# OwlPedal2.net
KiCad netlist of a schematic drawn in EAGLE
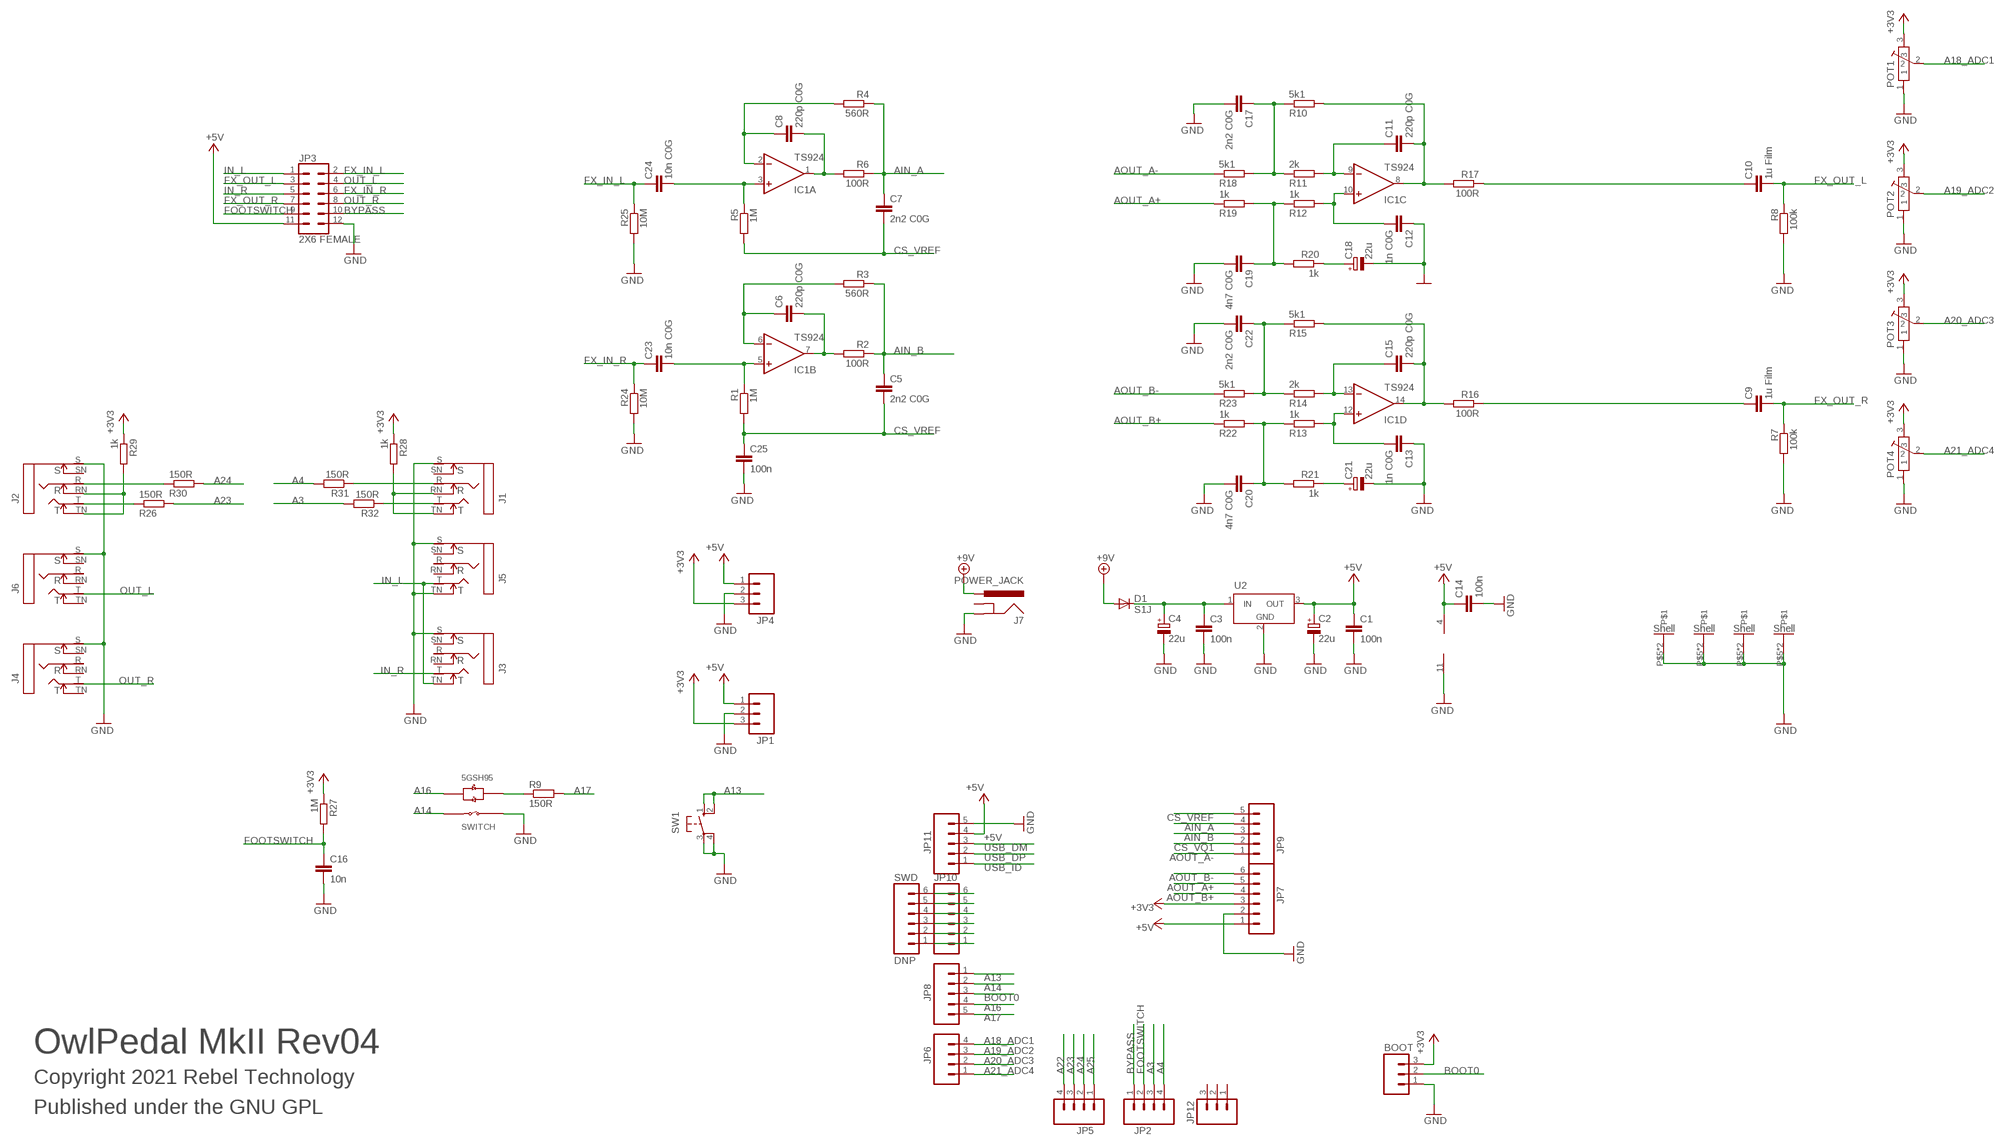
[diagram p0: schematic, sheet 1]

(export (version "E")
  (design (tool "Eeschema 10.0.6"))
  (components
    (comp (ref "BOOT")
      (value "M03PTH")
      (footprint "eagle-import:1X03")
      (libsource (lib "eagle-import") (part "M03PTH"))
    )
    (comp (ref "C1")
      (value "100n")
      (footprint "eagle-import:C0603")
      (libsource (lib "eagle-import") (part "C-EUC0603"))
    )
    (comp (ref "C2")
      (value "22u")
      (footprint "eagle-import:CPOL-5")
      (libsource (lib "eagle-import") (part "CPOL-EU153CLV-0505"))
    )
    (comp (ref "C3")
      (value "100n")
      (footprint "eagle-import:C0603")
      (libsource (lib "eagle-import") (part "C-EUC0603"))
    )
    (comp (ref "C4")
      (value "22u")
      (footprint "eagle-import:CPOL-5")
      (libsource (lib "eagle-import") (part "CPOL-EU153CLV-0505"))
    )
    (comp (ref "C5")
      (value "2n2 C0G")
      (footprint "eagle-import:C0603")
      (libsource (lib "eagle-import") (part "resistor_C-EUC0603"))
    )
    (comp (ref "C6")
      (value "220p C0G")
      (footprint "eagle-import:C0603")
      (libsource (lib "eagle-import") (part "resistor_C-EUC0603"))
    )
    (comp (ref "C7")
      (value "2n2 C0G")
      (footprint "eagle-import:C0603")
      (libsource (lib "eagle-import") (part "resistor_C-EUC0603"))
    )
    (comp (ref "C8")
      (value "220p C0G")
      (footprint "eagle-import:C0603")
      (libsource (lib "eagle-import") (part "resistor_C-EUC0603"))
    )
    (comp (ref "C9")
      (value "1u Film")
      (footprint "eagle-import:C1210")
      (libsource (lib "eagle-import") (part "C-EUC1210"))
    )
    (comp (ref "C10")
      (value "1u Film")
      (footprint "eagle-import:C1210")
      (libsource (lib "eagle-import") (part "C-EUC1210"))
    )
    (comp (ref "C11")
      (value "220p C0G")
      (footprint "eagle-import:C0603")
      (libsource (lib "eagle-import") (part "resistor_C-EUC0603"))
    )
    (comp (ref "C12")
      (value "1n C0G")
      (footprint "eagle-import:C0603")
      (libsource (lib "eagle-import") (part "resistor_C-EUC0603"))
    )
    (comp (ref "C13")
      (value "1n C0G")
      (footprint "eagle-import:C0603")
      (libsource (lib "eagle-import") (part "resistor_C-EUC0603"))
    )
    (comp (ref "C14")
      (value "100n")
      (footprint "eagle-import:C0603")
      (libsource (lib "eagle-import") (part "resistor_C-EUC0603"))
    )
    (comp (ref "C15")
      (value "220p C0G")
      (footprint "eagle-import:C0603")
      (libsource (lib "eagle-import") (part "resistor_C-EUC0603"))
    )
    (comp (ref "C16")
      (value "10n")
      (footprint "eagle-import:C0603")
      (libsource (lib "eagle-import") (part "Rebel_15457297_C-EUC0603"))
    )
    (comp (ref "C17")
      (value "2n2 C0G")
      (footprint "eagle-import:C0603")
      (libsource (lib "eagle-import") (part "resistor_C-EUC0603"))
    )
    (comp (ref "C18")
      (value "22u")
      (footprint "eagle-import:CPOL-5")
      (libsource (lib "eagle-import") (part "CPOL-EU153CLV-0505"))
    )
    (comp (ref "C19")
      (value "4n7 C0G")
      (footprint "eagle-import:C0603")
      (libsource (lib "eagle-import") (part "resistor_C-EUC0603"))
    )
    (comp (ref "C20")
      (value "4n7 C0G")
      (footprint "eagle-import:C0603")
      (libsource (lib "eagle-import") (part "resistor_C-EUC0603"))
    )
    (comp (ref "C21")
      (value "22u")
      (footprint "eagle-import:CPOL-5")
      (libsource (lib "eagle-import") (part "CPOL-EU153CLV-0505"))
    )
    (comp (ref "C22")
      (value "2n2 C0G")
      (footprint "eagle-import:C0603")
      (libsource (lib "eagle-import") (part "resistor_C-EUC0603"))
    )
    (comp (ref "C23")
      (value "10n C0G")
      (footprint "eagle-import:C0603")
      (libsource (lib "eagle-import") (part "C-EUC0603"))
    )
    (comp (ref "C24")
      (value "10n C0G")
      (footprint "eagle-import:C0603")
      (libsource (lib "eagle-import") (part "C-EUC0603"))
    )
    (comp (ref "C25")
      (value "100n")
      (footprint "eagle-import:C0603")
      (libsource (lib "eagle-import") (part "C-EUC0603"))
    )
    (comp (ref "D1")
      (value "S1J")
      (footprint "eagle-import:SMA-DIODE")
      (libsource (lib "eagle-import") (part "DIODESMA"))
    )
    (comp (ref "IC1")
      (value "TS924")
      (footprint "eagle-import:SO14")
      (libsource (lib "eagle-import") (part "LM324D"))
    )
    (comp (ref "J1")
      (value "NEUTRIK_NMJ6HCD2")
      (footprint "eagle-import:NMJ6HCD2")
      (libsource (lib "eagle-import") (part "NEUTRIK_NMJ6HCD2"))
    )
    (comp (ref "J2")
      (value "NEUTRIK_NMJ6HCD2")
      (footprint "eagle-import:NMJ6HCD2")
      (libsource (lib "eagle-import") (part "NEUTRIK_NMJ6HCD2"))
    )
    (comp (ref "J3")
      (value "NEUTRIK_NMJ6HCD2")
      (footprint "eagle-import:NMJ6HCD2")
      (libsource (lib "eagle-import") (part "NEUTRIK_NMJ6HCD2"))
    )
    (comp (ref "J4")
      (value "NEUTRIK_NMJ6HCD2")
      (footprint "eagle-import:NMJ6HCD2")
      (libsource (lib "eagle-import") (part "NEUTRIK_NMJ6HCD2"))
    )
    (comp (ref "J5")
      (value "NEUTRIK_NMJ6HCD2")
      (footprint "eagle-import:NMJ6HCD2")
      (libsource (lib "eagle-import") (part "NEUTRIK_NMJ6HCD2"))
    )
    (comp (ref "J6")
      (value "NEUTRIK_NMJ6HCD2")
      (footprint "eagle-import:NMJ6HCD2")
      (libsource (lib "eagle-import") (part "NEUTRIK_NMJ6HCD2"))
    )
    (comp (ref "J7")
      (value "POWER_JACK")
      (footprint "eagle-import:DC_JACK_SLOT")
      (libsource (lib "eagle-import") (part "POWER_JACK"))
    )
    (comp (ref "JP1")
      (value "M03PTH")
      (footprint "eagle-import:1X03")
      (libsource (lib "eagle-import") (part "M03PTH"))
    )
    (comp (ref "JP2")
      (value "M04PTH")
      (footprint "eagle-import:1X04")
      (libsource (lib "eagle-import") (part "M04PTH"))
    )
    (comp (ref "JP3")
      (value "2X6 FEMALE")
      (footprint "eagle-import:2X6")
      (libsource (lib "eagle-import") (part "CONN_06X2PTH_FEMALE"))
    )
    (comp (ref "JP4")
      (value "M03PTH")
      (footprint "eagle-import:1X03")
      (libsource (lib "eagle-import") (part "M03PTH"))
    )
    (comp (ref "JP5")
      (value "M04PTH")
      (footprint "eagle-import:1X04")
      (libsource (lib "eagle-import") (part "M04PTH"))
    )
    (comp (ref "JP6")
      (value "M04PTH")
      (footprint "eagle-import:1X04")
      (libsource (lib "eagle-import") (part "M04PTH"))
    )
    (comp (ref "JP7")
      (value "M06SIP")
      (footprint "eagle-import:1X06")
      (libsource (lib "eagle-import") (part "M06SIP"))
    )
    (comp (ref "JP8")
      (value "M05PTH")
      (footprint "eagle-import:1X05")
      (libsource (lib "eagle-import") (part "M05PTH"))
    )
    (comp (ref "JP9")
      (value "M05PTH")
      (footprint "eagle-import:1X05")
      (libsource (lib "eagle-import") (part "M05PTH"))
    )
    (comp (ref "JP10")
      (value "M06SIP")
      (footprint "eagle-import:1X06")
      (libsource (lib "eagle-import") (part "M06SIP"))
    )
    (comp (ref "JP11")
      (value "M05PTH")
      (footprint "eagle-import:1X05")
      (libsource (lib "eagle-import") (part "M05PTH"))
    )
    (comp (ref "JP12")
      (value "M03PTH")
      (footprint "eagle-import:1X03")
      (libsource (lib "eagle-import") (part "M03PTH"))
    )
    (comp (ref "POT1")
      (value "POT-ALPS-RK09L1140")
      (footprint "eagle-import:POT-ALPS-RK09L1140")
      (libsource (lib "eagle-import") (part "POT-ALPS-RK09L1140"))
    )
    (comp (ref "POT2")
      (value "POT-ALPS-RK09L1140")
      (footprint "eagle-import:POT-ALPS-RK09L1140")
      (libsource (lib "eagle-import") (part "POT-ALPS-RK09L1140"))
    )
    (comp (ref "POT3")
      (value "POT-ALPS-RK09L1140")
      (footprint "eagle-import:POT-ALPS-RK09L1140")
      (libsource (lib "eagle-import") (part "POT-ALPS-RK09L1140"))
    )
    (comp (ref "POT4")
      (value "POT-ALPS-RK09L1140")
      (footprint "eagle-import:POT-ALPS-RK09L1140")
      (libsource (lib "eagle-import") (part "POT-ALPS-RK09L1140"))
    )
    (comp (ref "R1")
      (value "1M")
      (footprint "eagle-import:0603")
      (libsource (lib "eagle-import") (part "R-EU_0603"))
    )
    (comp (ref "R2")
      (value "100R")
      (footprint "eagle-import:0603")
      (libsource (lib "eagle-import") (part "R-EU_0603"))
    )
    (comp (ref "R3")
      (value "560R")
      (footprint "eagle-import:0603")
      (libsource (lib "eagle-import") (part "R-EU_0603"))
    )
    (comp (ref "R4")
      (value "560R")
      (footprint "eagle-import:0603")
      (libsource (lib "eagle-import") (part "R-EU_0603"))
    )
    (comp (ref "R5")
      (value "1M")
      (footprint "eagle-import:0603")
      (libsource (lib "eagle-import") (part "R-EU_0603"))
    )
    (comp (ref "R6")
      (value "100R")
      (footprint "eagle-import:0603")
      (libsource (lib "eagle-import") (part "R-EU_0603"))
    )
    (comp (ref "R7")
      (value "100k")
      (footprint "eagle-import:0603")
      (libsource (lib "eagle-import") (part "R-EU_0603"))
    )
    (comp (ref "R8")
      (value "100k")
      (footprint "eagle-import:0603")
      (libsource (lib "eagle-import") (part "R-EU_0603"))
    )
    (comp (ref "R9")
      (value "150R")
      (footprint "eagle-import:0603")
      (libsource (lib "eagle-import") (part "R-EU_0603"))
    )
    (comp (ref "R10")
      (value "5k1")
      (footprint "eagle-import:0603")
      (libsource (lib "eagle-import") (part "R-EU_0603"))
    )
    (comp (ref "R11")
      (value "2k")
      (footprint "eagle-import:0603")
      (libsource (lib "eagle-import") (part "R-EU_0603"))
    )
    (comp (ref "R12")
      (value "1k")
      (footprint "eagle-import:0603")
      (libsource (lib "eagle-import") (part "R-EU_0603"))
    )
    (comp (ref "R13")
      (value "1k")
      (footprint "eagle-import:0603")
      (libsource (lib "eagle-import") (part "R-EU_0603"))
    )
    (comp (ref "R14")
      (value "2k")
      (footprint "eagle-import:0603")
      (libsource (lib "eagle-import") (part "R-EU_0603"))
    )
    (comp (ref "R15")
      (value "5k1")
      (footprint "eagle-import:0603")
      (libsource (lib "eagle-import") (part "R-EU_0603"))
    )
    (comp (ref "R16")
      (value "100R")
      (footprint "eagle-import:0603")
      (libsource (lib "eagle-import") (part "R-EU_0603"))
    )
    (comp (ref "R17")
      (value "100R")
      (footprint "eagle-import:0603")
      (libsource (lib "eagle-import") (part "R-EU_0603"))
    )
    (comp (ref "R18")
      (value "5k1")
      (footprint "eagle-import:0603")
      (libsource (lib "eagle-import") (part "R-EU_0603"))
    )
    (comp (ref "R19")
      (value "1k")
      (footprint "eagle-import:0603")
      (libsource (lib "eagle-import") (part "R-EU_0603"))
    )
    (comp (ref "R20")
      (value "1k")
      (footprint "eagle-import:0603")
      (libsource (lib "eagle-import") (part "R-EU_0603"))
    )
    (comp (ref "R21")
      (value "1k")
      (footprint "eagle-import:0603")
      (libsource (lib "eagle-import") (part "R-EU_0603"))
    )
    (comp (ref "R22")
      (value "1k")
      (footprint "eagle-import:0603")
      (libsource (lib "eagle-import") (part "R-EU_0603"))
    )
    (comp (ref "R23")
      (value "5k1")
      (footprint "eagle-import:0603")
      (libsource (lib "eagle-import") (part "R-EU_0603"))
    )
    (comp (ref "R24")
      (value "10M")
      (footprint "eagle-import:0603")
      (libsource (lib "eagle-import") (part "R-EU_0603"))
    )
    (comp (ref "R25")
      (value "10M")
      (footprint "eagle-import:0603")
      (libsource (lib "eagle-import") (part "R-EU_0603"))
    )
    (comp (ref "R26")
      (value "150R")
      (footprint "eagle-import:0603")
      (libsource (lib "eagle-import") (part "R-EU_0603"))
    )
    (comp (ref "R27")
      (value "1M")
      (footprint "eagle-import:0603")
      (libsource (lib "eagle-import") (part "R-EU_0603"))
    )
    (comp (ref "R28")
      (value "1k")
      (footprint "eagle-import:0603")
      (libsource (lib "eagle-import") (part "R-EU_0603"))
    )
    (comp (ref "R29")
      (value "1k")
      (footprint "eagle-import:0603")
      (libsource (lib "eagle-import") (part "R-EU_0603"))
    )
    (comp (ref "R30")
      (value "150R")
      (footprint "eagle-import:0603")
      (libsource (lib "eagle-import") (part "R-EU_0603"))
    )
    (comp (ref "R31")
      (value "150R")
      (footprint "eagle-import:0603")
      (libsource (lib "eagle-import") (part "R-EU_0603"))
    )
    (comp (ref "R32")
      (value "150R")
      (footprint "eagle-import:0603")
      (libsource (lib "eagle-import") (part "R-EU_0603"))
    )
    (comp (ref "SW1")
      (value "10-XX")
      (footprint "eagle-import:B3F-10XX")
      (fields (field (name "MPN") "B3F-1000"))
      (libsource (lib "eagle-import") (part "10-XX"))
    )
    (comp (ref "SW2")
      (value "5GTH9")
      (footprint "eagle-import:5GTH9")
      (libsource (lib "eagle-import") (part "5GTH9"))
    )
    (comp (ref "SWD")
      (value "DNP")
      (footprint "eagle-import:1X06")
      (libsource (lib "eagle-import") (part "M06SIP"))
    )
    (comp (ref "U2")
      (value "TSR-1-2450")
      (footprint "eagle-import:TSR-1-2450")
      (libsource (lib "eagle-import") (part "TSR-1-2450"))
    )
  )
  (nets
    (net (code "1") (name "+3V3") (class "Default")
      (node (ref "BOOT") (pin "3") (pinfunction "3_3") (pintype "passive"))
      (node (ref "JP1") (pin "3") (pinfunction "3_3") (pintype "passive"))
      (node (ref "JP4") (pin "3") (pinfunction "3_3") (pintype "passive"))
      (node (ref "JP7") (pin "3") (pinfunction "3_3") (pintype "passive"))
      (node (ref "POT1") (pin "3") (pinfunction "3_3") (pintype "bidirectional"))
      (node (ref "POT2") (pin "3") (pinfunction "3_3") (pintype "bidirectional"))
      (node (ref "POT3") (pin "3") (pinfunction "3_3") (pintype "bidirectional"))
      (node (ref "POT4") (pin "3") (pinfunction "3_3") (pintype "bidirectional"))
      (node (ref "R27") (pin "1") (pinfunction "1_1") (pintype "passive"))
      (node (ref "R28") (pin "1") (pinfunction "1_1") (pintype "passive"))
      (node (ref "R29") (pin "1") (pinfunction "1_1") (pintype "passive"))
    )
    (net (code "2") (name "+5V") (class "Default")
      (node (ref "C1") (pin "1") (pinfunction "1_1") (pintype "passive"))
      (node (ref "C14") (pin "1") (pinfunction "1_1") (pintype "passive"))
      (node (ref "C2") (pin "+") (pinfunction "+_+") (pintype "passive"))
      (node (ref "IC1") (pin "4") (pinfunction "V+_4") (pintype "power_in"))
      (node (ref "JP1") (pin "1") (pinfunction "1_1") (pintype "passive"))
      (node (ref "JP11") (pin "4") (pinfunction "4_4") (pintype "passive"))
      (node (ref "JP3") (pin "11") (pinfunction "11_11") (pintype "passive"))
      (node (ref "JP4") (pin "1") (pinfunction "1_1") (pintype "passive"))
      (node (ref "JP7") (pin "1") (pinfunction "1_1") (pintype "passive"))
      (node (ref "U2") (pin "3") (pinfunction "OUT_3") (pintype "output"))
    )
    (net (code "3") (name "+9V") (class "Default")
      (node (ref "D1") (pin "A") (pinfunction "A_A") (pintype "passive"))
      (node (ref "J7") (pin "PWR") (pinfunction "PWR_PWR") (pintype "bidirectional"))
    )
    (net (code "4") (name "/A3") (class "Default")
      (node (ref "JP2") (pin "3") (pinfunction "3_3") (pintype "passive"))
      (node (ref "R32") (pin "2") (pinfunction "2_2") (pintype "passive"))
    )
    (net (code "5") (name "/A4") (class "Default")
      (node (ref "JP2") (pin "4") (pinfunction "4_4") (pintype "passive"))
      (node (ref "R31") (pin "2") (pinfunction "2_2") (pintype "passive"))
    )
    (net (code "6") (name "/A13") (class "Default")
      (node (ref "JP8") (pin "1") (pinfunction "1_1") (pintype "passive"))
      (node (ref "SW1") (pin "1") (pinfunction "S_1") (pintype "passive"))
      (node (ref "SW1") (pin "2") (pinfunction "S1_2") (pintype "passive"))
    )
    (net (code "7") (name "/A14") (class "Default")
      (node (ref "JP8") (pin "2") (pinfunction "2_2") (pintype "passive"))
      (node (ref "SW2") (pin "4") (pinfunction "SWITCH_A_4") (pintype "power_in"))
    )
    (net (code "8") (name "/A16") (class "Default")
      (node (ref "JP8") (pin "4") (pinfunction "4_4") (pintype "passive"))
      (node (ref "SW2") (pin "-2") (pinfunction "LED_G+_-2") (pintype "input"))
    )
    (net (code "9") (name "/A17") (class "Default")
      (node (ref "JP8") (pin "5") (pinfunction "5_5") (pintype "passive"))
      (node (ref "R9") (pin "2") (pinfunction "2_2") (pintype "passive"))
    )
    (net (code "10") (name "/A18_ADC1") (class "Default")
      (node (ref "JP6") (pin "4") (pinfunction "4_4") (pintype "passive"))
      (node (ref "POT1") (pin "2") (pinfunction "2_2") (pintype "bidirectional"))
    )
    (net (code "11") (name "/A19_ADC2") (class "Default")
      (node (ref "JP6") (pin "3") (pinfunction "3_3") (pintype "passive"))
      (node (ref "POT2") (pin "2") (pinfunction "2_2") (pintype "bidirectional"))
    )
    (net (code "12") (name "/A20_ADC3") (class "Default")
      (node (ref "JP6") (pin "2") (pinfunction "2_2") (pintype "passive"))
      (node (ref "POT3") (pin "2") (pinfunction "2_2") (pintype "bidirectional"))
    )
    (net (code "13") (name "/A21_ADC4") (class "Default")
      (node (ref "JP6") (pin "1") (pinfunction "1_1") (pintype "passive"))
      (node (ref "POT4") (pin "2") (pinfunction "2_2") (pintype "bidirectional"))
    )
    (net (code "14") (name "/A22") (class "Default")
      (node (ref "JP5") (pin "4") (pinfunction "4_4") (pintype "passive"))
    )
    (net (code "15") (name "/A23") (class "Default")
      (node (ref "JP5") (pin "3") (pinfunction "3_3") (pintype "passive"))
      (node (ref "R26") (pin "2") (pinfunction "2_2") (pintype "passive"))
    )
    (net (code "16") (name "/A24") (class "Default")
      (node (ref "JP5") (pin "2") (pinfunction "2_2") (pintype "passive"))
      (node (ref "R30") (pin "2") (pinfunction "2_2") (pintype "passive"))
    )
    (net (code "17") (name "/A25") (class "Default")
      (node (ref "JP5") (pin "1") (pinfunction "1_1") (pintype "passive"))
    )
    (net (code "18") (name "/AIN_A") (class "Default")
      (node (ref "C7") (pin "1") (pinfunction "1_1") (pintype "passive"))
      (node (ref "JP9") (pin "4") (pinfunction "4_4") (pintype "passive"))
      (node (ref "R4") (pin "1") (pinfunction "1_1") (pintype "passive"))
      (node (ref "R6") (pin "1") (pinfunction "1_1") (pintype "passive"))
    )
    (net (code "19") (name "/AIN_B") (class "Default")
      (node (ref "C5") (pin "1") (pinfunction "1_1") (pintype "passive"))
      (node (ref "JP9") (pin "3") (pinfunction "3_3") (pintype "passive"))
      (node (ref "R2") (pin "1") (pinfunction "1_1") (pintype "passive"))
      (node (ref "R3") (pin "1") (pinfunction "1_1") (pintype "passive"))
    )
    (net (code "20") (name "/AOUT_A+") (class "Default")
      (node (ref "JP7") (pin "5") (pinfunction "5_5") (pintype "passive"))
      (node (ref "R19") (pin "1") (pinfunction "1_1") (pintype "passive"))
    )
    (net (code "21") (name "/AOUT_A-") (class "Default")
      (node (ref "JP9") (pin "1") (pinfunction "1_1") (pintype "passive"))
      (node (ref "R18") (pin "1") (pinfunction "1_1") (pintype "passive"))
    )
    (net (code "22") (name "/AOUT_B+") (class "Default")
      (node (ref "JP7") (pin "4") (pinfunction "4_4") (pintype "passive"))
      (node (ref "R22") (pin "1") (pinfunction "1_1") (pintype "passive"))
    )
    (net (code "23") (name "/AOUT_B-") (class "Default")
      (node (ref "JP7") (pin "6") (pinfunction "6_6") (pintype "passive"))
      (node (ref "R23") (pin "1") (pinfunction "1_1") (pintype "passive"))
    )
    (net (code "24") (name "/BOOT0") (class "Default")
      (node (ref "BOOT") (pin "2") (pinfunction "2_2") (pintype "passive"))
      (node (ref "JP8") (pin "3") (pinfunction "3_3") (pintype "passive"))
    )
    (net (code "25") (name "/BYPASS") (class "Default")
      (node (ref "JP2") (pin "1") (pinfunction "1_1") (pintype "passive"))
      (node (ref "JP3") (pin "10") (pinfunction "10_10") (pintype "passive"))
    )
    (net (code "26") (name "/CS_VQ1") (class "Default")
      (node (ref "JP9") (pin "2") (pinfunction "2_2") (pintype "passive"))
    )
    (net (code "27") (name "/CS_VREF") (class "Default")
      (node (ref "C25") (pin "1") (pinfunction "1_1") (pintype "passive"))
      (node (ref "C5") (pin "2") (pinfunction "2_2") (pintype "passive"))
      (node (ref "C7") (pin "2") (pinfunction "2_2") (pintype "passive"))
      (node (ref "JP9") (pin "5") (pinfunction "5_5") (pintype "passive"))
      (node (ref "R1") (pin "2") (pinfunction "2_2") (pintype "passive"))
      (node (ref "R5") (pin "2") (pinfunction "2_2") (pintype "passive"))
    )
    (net (code "28") (name "/FOOTSWITCH") (class "Default")
      (node (ref "C16") (pin "1") (pinfunction "1_1") (pintype "passive"))
      (node (ref "JP2") (pin "2") (pinfunction "2_2") (pintype "passive"))
      (node (ref "JP3") (pin "9") (pinfunction "9_9") (pintype "passive"))
      (node (ref "R27") (pin "2") (pinfunction "2_2") (pintype "passive"))
    )
    (net (code "29") (name "/FX_IN_L") (class "Default")
      (node (ref "C24") (pin "2") (pinfunction "2_2") (pintype "passive"))
      (node (ref "JP3") (pin "2") (pinfunction "2_2") (pintype "passive"))
      (node (ref "R25") (pin "1") (pinfunction "1_1") (pintype "passive"))
    )
    (net (code "30") (name "/FX_IN_R") (class "Default")
      (node (ref "C23") (pin "2") (pinfunction "2_2") (pintype "passive"))
      (node (ref "JP3") (pin "6") (pinfunction "6_6") (pintype "passive"))
      (node (ref "R24") (pin "1") (pinfunction "1_1") (pintype "passive"))
    )
    (net (code "31") (name "/FX_OUT_L") (class "Default")
      (node (ref "C10") (pin "2") (pinfunction "2_2") (pintype "passive"))
      (node (ref "JP3") (pin "3") (pinfunction "3_3") (pintype "passive"))
      (node (ref "R8") (pin "1") (pinfunction "1_1") (pintype "passive"))
    )
    (net (code "32") (name "/FX_OUT_R") (class "Default")
      (node (ref "C9") (pin "2") (pinfunction "2_2") (pintype "passive"))
      (node (ref "JP3") (pin "7") (pinfunction "7_7") (pintype "passive"))
      (node (ref "R7") (pin "1") (pinfunction "1_1") (pintype "passive"))
    )
    (net (code "33") (name "/IN_L") (class "Default")
      (node (ref "J3") (pin "TN") (pinfunction "TN_TN") (pintype "passive"))
      (node (ref "J5") (pin "T") (pinfunction "T_T") (pintype "passive"))
      (node (ref "JP3") (pin "1") (pinfunction "1_1") (pintype "passive"))
    )
    (net (code "34") (name "/IN_R") (class "Default")
      (node (ref "J3") (pin "T") (pinfunction "T_T") (pintype "passive"))
      (node (ref "JP3") (pin "5") (pinfunction "5_5") (pintype "passive"))
    )
    (net (code "35") (name "/OUT_L") (class "Default")
      (node (ref "J6") (pin "T") (pinfunction "T_T") (pintype "passive"))
      (node (ref "JP3") (pin "4") (pinfunction "4_4") (pintype "passive"))
    )
    (net (code "36") (name "/OUT_R") (class "Default")
      (node (ref "J4") (pin "T") (pinfunction "T_T") (pintype "passive"))
      (node (ref "JP3") (pin "8") (pinfunction "8_8") (pintype "passive"))
    )
    (net (code "37") (name "/USB_DM") (class "Default")
      (node (ref "JP11") (pin "3") (pinfunction "3_3") (pintype "passive"))
    )
    (net (code "38") (name "/USB_DP") (class "Default")
      (node (ref "JP11") (pin "2") (pinfunction "2_2") (pintype "passive"))
    )
    (net (code "39") (name "/USB_ID") (class "Default")
      (node (ref "JP11") (pin "1") (pinfunction "1_1") (pintype "passive"))
    )
    (net (code "40") (name "GND") (class "Default")
      (node (ref "BOOT") (pin "1") (pinfunction "1_1") (pintype "passive"))
      (node (ref "C1") (pin "2") (pinfunction "2_2") (pintype "passive"))
      (node (ref "C12") (pin "1") (pinfunction "1_1") (pintype "passive"))
      (node (ref "C13") (pin "1") (pinfunction "1_1") (pintype "passive"))
      (node (ref "C14") (pin "2") (pinfunction "2_2") (pintype "passive"))
      (node (ref "C16") (pin "2") (pinfunction "2_2") (pintype "passive"))
      (node (ref "C17") (pin "2") (pinfunction "2_2") (pintype "passive"))
      (node (ref "C18") (pin "-") (pinfunction "-_-") (pintype "passive"))
      (node (ref "C19") (pin "2") (pinfunction "2_2") (pintype "passive"))
      (node (ref "C2") (pin "-") (pinfunction "-_-") (pintype "passive"))
      (node (ref "C20") (pin "2") (pinfunction "2_2") (pintype "passive"))
      (node (ref "C21") (pin "-") (pinfunction "-_-") (pintype "passive"))
      (node (ref "C22") (pin "2") (pinfunction "2_2") (pintype "passive"))
      (node (ref "C25") (pin "2") (pinfunction "2_2") (pintype "passive"))
      (node (ref "C3") (pin "2") (pinfunction "2_2") (pintype "passive"))
      (node (ref "C4") (pin "-") (pinfunction "-_-") (pintype "passive"))
      (node (ref "IC1") (pin "11") (pinfunction "V-_11") (pintype "power_in"))
      (node (ref "J1") (pin "S") (pinfunction "S_S") (pintype "passive"))
      (node (ref "J2") (pin "S") (pinfunction "S_S") (pintype "passive"))
      (node (ref "J3") (pin "S") (pinfunction "S_S") (pintype "passive"))
      (node (ref "J4") (pin "S") (pinfunction "S_S") (pintype "passive"))
      (node (ref "J5") (pin "S") (pinfunction "S_S") (pintype "passive"))
      (node (ref "J5") (pin "TN") (pinfunction "TN_TN") (pintype "passive"))
      (node (ref "J6") (pin "S") (pinfunction "S_S") (pintype "passive"))
      (node (ref "J7") (pin "GND") (pinfunction "GND_GND") (pintype "bidirectional"))
      (node (ref "JP1") (pin "2") (pinfunction "2_2") (pintype "passive"))
      (node (ref "JP11") (pin "5") (pinfunction "5_5") (pintype "passive"))
      (node (ref "JP3") (pin "12") (pinfunction "12_12") (pintype "passive"))
      (node (ref "JP4") (pin "2") (pinfunction "2_2") (pintype "passive"))
      (node (ref "JP7") (pin "2") (pinfunction "2_2") (pintype "passive"))
      (node (ref "POT1") (pin "1") (pinfunction "1_1") (pintype "bidirectional"))
      (node (ref "POT1") (pin "P$5") (pinfunction "P$1_P$5") (pintype "bidirectional"))
      (node (ref "POT1") (pin "P$6") (pinfunction "P$1_P$6") (pintype "bidirectional"))
      (node (ref "POT2") (pin "1") (pinfunction "1_1") (pintype "bidirectional"))
      (node (ref "POT2") (pin "P$5") (pinfunction "P$1_P$5") (pintype "bidirectional"))
      (node (ref "POT2") (pin "P$6") (pinfunction "P$1_P$6") (pintype "bidirectional"))
      (node (ref "POT3") (pin "1") (pinfunction "1_1") (pintype "bidirectional"))
      (node (ref "POT3") (pin "P$5") (pinfunction "P$1_P$5") (pintype "bidirectional"))
      (node (ref "POT3") (pin "P$6") (pinfunction "P$1_P$6") (pintype "bidirectional"))
      (node (ref "POT4") (pin "1") (pinfunction "1_1") (pintype "bidirectional"))
      (node (ref "POT4") (pin "P$5") (pinfunction "P$1_P$5") (pintype "bidirectional"))
      (node (ref "POT4") (pin "P$6") (pinfunction "P$1_P$6") (pintype "bidirectional"))
      (node (ref "R24") (pin "2") (pinfunction "2_2") (pintype "passive"))
      (node (ref "R25") (pin "2") (pinfunction "2_2") (pintype "passive"))
      (node (ref "R7") (pin "2") (pinfunction "2_2") (pintype "passive"))
      (node (ref "R8") (pin "2") (pinfunction "2_2") (pintype "passive"))
      (node (ref "SW1") (pin "3") (pinfunction "P_3") (pintype "passive"))
      (node (ref "SW1") (pin "4") (pinfunction "P1_4") (pintype "passive"))
      (node (ref "SW2") (pin "1") (pinfunction "SWITCH_B_1") (pintype "power_in"))
      (node (ref "U2") (pin "2") (pinfunction "GND_2") (pintype "power_in"))
    )
    (net (code "41") (name "Net-(C9-Pad1)") (class "Default")
      (node (ref "C9") (pin "1") (pinfunction "1_1") (pintype "passive"))
      (node (ref "R16") (pin "1") (pinfunction "1_1") (pintype "passive"))
    )
    (net (code "42") (name "Net-(C10-Pad1)") (class "Default")
      (node (ref "C10") (pin "1") (pinfunction "1_1") (pintype "passive"))
      (node (ref "R17") (pin "1") (pinfunction "1_1") (pintype "passive"))
    )
    (net (code "43") (name "Net-(C17-Pad1)") (class "Default")
      (node (ref "C17") (pin "1") (pinfunction "1_1") (pintype "passive"))
      (node (ref "R10") (pin "1") (pinfunction "1_1") (pintype "passive"))
      (node (ref "R11") (pin "1") (pinfunction "1_1") (pintype "passive"))
      (node (ref "R18") (pin "2") (pinfunction "2_2") (pintype "passive"))
    )
    (net (code "44") (name "Net-(C18-Pad+)") (class "Default")
      (node (ref "C18") (pin "+") (pinfunction "+_+") (pintype "passive"))
      (node (ref "R20") (pin "1") (pinfunction "1_1") (pintype "passive"))
    )
    (net (code "45") (name "Net-(C19-Pad1)") (class "Default")
      (node (ref "C19") (pin "1") (pinfunction "1_1") (pintype "passive"))
      (node (ref "R12") (pin "1") (pinfunction "1_1") (pintype "passive"))
      (node (ref "R19") (pin "2") (pinfunction "2_2") (pintype "passive"))
      (node (ref "R20") (pin "2") (pinfunction "2_2") (pintype "passive"))
    )
    (net (code "46") (name "Net-(C20-Pad1)") (class "Default")
      (node (ref "C20") (pin "1") (pinfunction "1_1") (pintype "passive"))
      (node (ref "R13") (pin "1") (pinfunction "1_1") (pintype "passive"))
      (node (ref "R21") (pin "2") (pinfunction "2_2") (pintype "passive"))
      (node (ref "R22") (pin "2") (pinfunction "2_2") (pintype "passive"))
    )
    (net (code "47") (name "Net-(C21-Pad+)") (class "Default")
      (node (ref "C21") (pin "+") (pinfunction "+_+") (pintype "passive"))
      (node (ref "R21") (pin "1") (pinfunction "1_1") (pintype "passive"))
    )
    (net (code "48") (name "Net-(C22-Pad1)") (class "Default")
      (node (ref "C22") (pin "1") (pinfunction "1_1") (pintype "passive"))
      (node (ref "R14") (pin "1") (pinfunction "1_1") (pintype "passive"))
      (node (ref "R15") (pin "1") (pinfunction "1_1") (pintype "passive"))
      (node (ref "R23") (pin "2") (pinfunction "2_2") (pintype "passive"))
    )
    (net (code "49") (name "Net-(IC1A-+IN)") (class "Default")
      (node (ref "C24") (pin "1") (pinfunction "1_1") (pintype "passive"))
      (node (ref "IC1") (pin "3") (pinfunction "+IN_3") (pintype "input"))
      (node (ref "R5") (pin "1") (pinfunction "1_1") (pintype "passive"))
    )
    (net (code "50") (name "Net-(IC1A--IN)") (class "Default")
      (node (ref "C8") (pin "1") (pinfunction "1_1") (pintype "passive"))
      (node (ref "IC1") (pin "2") (pinfunction "-IN_2") (pintype "input"))
      (node (ref "R4") (pin "2") (pinfunction "2_2") (pintype "passive"))
    )
    (net (code "51") (name "Net-(IC1A-OUT)") (class "Default")
      (node (ref "C8") (pin "2") (pinfunction "2_2") (pintype "passive"))
      (node (ref "IC1") (pin "1") (pinfunction "OUT_1") (pintype "output"))
      (node (ref "R6") (pin "2") (pinfunction "2_2") (pintype "passive"))
    )
    (net (code "52") (name "Net-(IC1B-+IN)") (class "Default")
      (node (ref "C23") (pin "1") (pinfunction "1_1") (pintype "passive"))
      (node (ref "IC1") (pin "5") (pinfunction "+IN_5") (pintype "input"))
      (node (ref "R1") (pin "1") (pinfunction "1_1") (pintype "passive"))
    )
    (net (code "53") (name "Net-(IC1B--IN)") (class "Default")
      (node (ref "C6") (pin "1") (pinfunction "1_1") (pintype "passive"))
      (node (ref "IC1") (pin "6") (pinfunction "-IN_6") (pintype "input"))
      (node (ref "R3") (pin "2") (pinfunction "2_2") (pintype "passive"))
    )
    (net (code "54") (name "Net-(IC1B-OUT)") (class "Default")
      (node (ref "C6") (pin "2") (pinfunction "2_2") (pintype "passive"))
      (node (ref "IC1") (pin "7") (pinfunction "OUT_7") (pintype "output"))
      (node (ref "R2") (pin "2") (pinfunction "2_2") (pintype "passive"))
    )
    (net (code "55") (name "Net-(IC1C-+IN)") (class "Default")
      (node (ref "C12") (pin "2") (pinfunction "2_2") (pintype "passive"))
      (node (ref "IC1") (pin "10") (pinfunction "+IN_10") (pintype "input"))
      (node (ref "R12") (pin "2") (pinfunction "2_2") (pintype "passive"))
    )
    (net (code "56") (name "Net-(IC1C--IN)") (class "Default")
      (node (ref "C11") (pin "1") (pinfunction "1_1") (pintype "passive"))
      (node (ref "IC1") (pin "9") (pinfunction "-IN_9") (pintype "input"))
      (node (ref "R11") (pin "2") (pinfunction "2_2") (pintype "passive"))
    )
    (net (code "57") (name "Net-(IC1C-OUT)") (class "Default")
      (node (ref "C11") (pin "2") (pinfunction "2_2") (pintype "passive"))
      (node (ref "IC1") (pin "8") (pinfunction "OUT_8") (pintype "output"))
      (node (ref "R10") (pin "2") (pinfunction "2_2") (pintype "passive"))
      (node (ref "R17") (pin "2") (pinfunction "2_2") (pintype "passive"))
    )
    (net (code "58") (name "Net-(IC1D-+IN)") (class "Default")
      (node (ref "C13") (pin "2") (pinfunction "2_2") (pintype "passive"))
      (node (ref "IC1") (pin "12") (pinfunction "+IN_12") (pintype "input"))
      (node (ref "R13") (pin "2") (pinfunction "2_2") (pintype "passive"))
    )
    (net (code "59") (name "Net-(IC1D--IN)") (class "Default")
      (node (ref "C15") (pin "1") (pinfunction "1_1") (pintype "passive"))
      (node (ref "IC1") (pin "13") (pinfunction "-IN_13") (pintype "input"))
      (node (ref "R14") (pin "2") (pinfunction "2_2") (pintype "passive"))
    )
    (net (code "60") (name "Net-(IC1D-OUT)") (class "Default")
      (node (ref "C15") (pin "2") (pinfunction "2_2") (pintype "passive"))
      (node (ref "IC1") (pin "14") (pinfunction "OUT_14") (pintype "output"))
      (node (ref "R15") (pin "2") (pinfunction "2_2") (pintype "passive"))
      (node (ref "R16") (pin "2") (pinfunction "2_2") (pintype "passive"))
    )
    (net (code "61") (name "Net-(J1-PadR)") (class "Default")
      (node (ref "J1") (pin "R") (pinfunction "R_R") (pintype "passive"))
      (node (ref "R31") (pin "1") (pinfunction "1_1") (pintype "passive"))
    )
    (net (code "62") (name "Net-(J1-PadRN)") (class "Default")
      (node (ref "J1") (pin "RN") (pinfunction "RN_RN") (pintype "passive"))
      (node (ref "J1") (pin "TN") (pinfunction "TN_TN") (pintype "passive"))
      (node (ref "R28") (pin "2") (pinfunction "2_2") (pintype "passive"))
    )
    (net (code "63") (name "Net-(J1-PadT)") (class "Default")
      (node (ref "J1") (pin "T") (pinfunction "T_T") (pintype "passive"))
      (node (ref "R32") (pin "1") (pinfunction "1_1") (pintype "passive"))
    )
    (net (code "64") (name "Net-(J2-PadR)") (class "Default")
      (node (ref "J2") (pin "R") (pinfunction "R_R") (pintype "passive"))
      (node (ref "R30") (pin "1") (pinfunction "1_1") (pintype "passive"))
    )
    (net (code "65") (name "Net-(J2-PadRN)") (class "Default")
      (node (ref "J2") (pin "RN") (pinfunction "RN_RN") (pintype "passive"))
      (node (ref "J2") (pin "TN") (pinfunction "TN_TN") (pintype "passive"))
      (node (ref "R29") (pin "2") (pinfunction "2_2") (pintype "passive"))
    )
    (net (code "66") (name "Net-(J2-PadT)") (class "Default")
      (node (ref "J2") (pin "T") (pinfunction "T_T") (pintype "passive"))
      (node (ref "R26") (pin "1") (pinfunction "1_1") (pintype "passive"))
    )
    (net (code "67") (name "Net-(JP10-Pad1)") (class "Default")
      (node (ref "JP10") (pin "1") (pinfunction "1_1") (pintype "passive"))
      (node (ref "SWD") (pin "1") (pinfunction "1_1") (pintype "passive"))
    )
    (net (code "68") (name "Net-(JP10-Pad2)") (class "Default")
      (node (ref "JP10") (pin "2") (pinfunction "2_2") (pintype "passive"))
      (node (ref "SWD") (pin "2") (pinfunction "2_2") (pintype "passive"))
    )
    (net (code "69") (name "Net-(JP10-Pad3)") (class "Default")
      (node (ref "JP10") (pin "3") (pinfunction "3_3") (pintype "passive"))
      (node (ref "SWD") (pin "3") (pinfunction "3_3") (pintype "passive"))
    )
    (net (code "70") (name "Net-(JP10-Pad4)") (class "Default")
      (node (ref "JP10") (pin "4") (pinfunction "4_4") (pintype "passive"))
      (node (ref "SWD") (pin "4") (pinfunction "4_4") (pintype "passive"))
    )
    (net (code "71") (name "Net-(JP10-Pad5)") (class "Default")
      (node (ref "JP10") (pin "5") (pinfunction "5_5") (pintype "passive"))
      (node (ref "SWD") (pin "5") (pinfunction "5_5") (pintype "passive"))
    )
    (net (code "72") (name "Net-(JP10-Pad6)") (class "Default")
      (node (ref "JP10") (pin "6") (pinfunction "6_6") (pintype "passive"))
      (node (ref "SWD") (pin "6") (pinfunction "6_6") (pintype "passive"))
    )
    (net (code "73") (name "Net-(SW2-LED_R+)") (class "Default")
      (node (ref "R9") (pin "1") (pinfunction "1_1") (pintype "passive"))
      (node (ref "SW2") (pin "+3") (pinfunction "LED_R+_+3") (pintype "input"))
    )
    (net (code "74") (name "Net-(U2-IN)") (class "Default")
      (node (ref "C3") (pin "1") (pinfunction "1_1") (pintype "passive"))
      (node (ref "C4") (pin "+") (pinfunction "+_+") (pintype "passive"))
      (node (ref "D1") (pin "C") (pinfunction "C_C") (pintype "passive"))
      (node (ref "U2") (pin "1") (pinfunction "IN_1") (pintype "input"))
    )
    (net (code "75") (name "unconnected-(J1-PadSN)") (class "Default")
      (node (ref "J1") (pin "SN") (pinfunction "SN_SN") (pintype "passive"))
    )
    (net (code "76") (name "unconnected-(J2-PadSN)") (class "Default")
      (node (ref "J2") (pin "SN") (pinfunction "SN_SN") (pintype "passive"))
    )
    (net (code "77") (name "unconnected-(J3-PadR)") (class "Default")
      (node (ref "J3") (pin "R") (pinfunction "R_R") (pintype "passive"))
    )
    (net (code "78") (name "unconnected-(J3-PadRN)") (class "Default")
      (node (ref "J3") (pin "RN") (pinfunction "RN_RN") (pintype "passive"))
    )
    (net (code "79") (name "unconnected-(J3-PadSN)") (class "Default")
      (node (ref "J3") (pin "SN") (pinfunction "SN_SN") (pintype "passive"))
    )
    (net (code "80") (name "unconnected-(J4-PadR)") (class "Default")
      (node (ref "J4") (pin "R") (pinfunction "R_R") (pintype "passive"))
    )
    (net (code "81") (name "unconnected-(J4-PadRN)") (class "Default")
      (node (ref "J4") (pin "RN") (pinfunction "RN_RN") (pintype "passive"))
    )
    (net (code "82") (name "unconnected-(J4-PadSN)") (class "Default")
      (node (ref "J4") (pin "SN") (pinfunction "SN_SN") (pintype "passive"))
    )
    (net (code "83") (name "unconnected-(J4-PadTN)") (class "Default")
      (node (ref "J4") (pin "TN") (pinfunction "TN_TN") (pintype "passive"))
    )
    (net (code "84") (name "unconnected-(J5-PadR)") (class "Default")
      (node (ref "J5") (pin "R") (pinfunction "R_R") (pintype "passive"))
    )
    (net (code "85") (name "unconnected-(J5-PadRN)") (class "Default")
      (node (ref "J5") (pin "RN") (pinfunction "RN_RN") (pintype "passive"))
    )
    (net (code "86") (name "unconnected-(J5-PadSN)") (class "Default")
      (node (ref "J5") (pin "SN") (pinfunction "SN_SN") (pintype "passive"))
    )
    (net (code "87") (name "unconnected-(J6-PadR)") (class "Default")
      (node (ref "J6") (pin "R") (pinfunction "R_R") (pintype "passive"))
    )
    (net (code "88") (name "unconnected-(J6-PadRN)") (class "Default")
      (node (ref "J6") (pin "RN") (pinfunction "RN_RN") (pintype "passive"))
    )
    (net (code "89") (name "unconnected-(J6-PadSN)") (class "Default")
      (node (ref "J6") (pin "SN") (pinfunction "SN_SN") (pintype "passive"))
    )
    (net (code "90") (name "unconnected-(J6-PadTN)") (class "Default")
      (node (ref "J6") (pin "TN") (pinfunction "TN_TN") (pintype "passive"))
    )
    (net (code "91") (name "unconnected-(J7-PadGNDBREAK)") (class "Default")
      (node (ref "J7") (pin "GNDBREAK") (pinfunction "GNDBREAK_GNDBREAK") (pintype "bidirectional"))
    )
    (net (code "92") (name "unconnected-(JP12-Pad1)") (class "Default")
      (node (ref "JP12") (pin "1") (pinfunction "1_1") (pintype "passive"))
    )
    (net (code "93") (name "unconnected-(JP12-Pad2)") (class "Default")
      (node (ref "JP12") (pin "2") (pinfunction "2_2") (pintype "passive"))
    )
    (net (code "94") (name "unconnected-(JP12-Pad3)") (class "Default")
      (node (ref "JP12") (pin "3") (pinfunction "3_3") (pintype "passive"))
    )
  )
)
